# Flipdot_segment.net
KiCad netlist of a schematic drawn in EAGLE
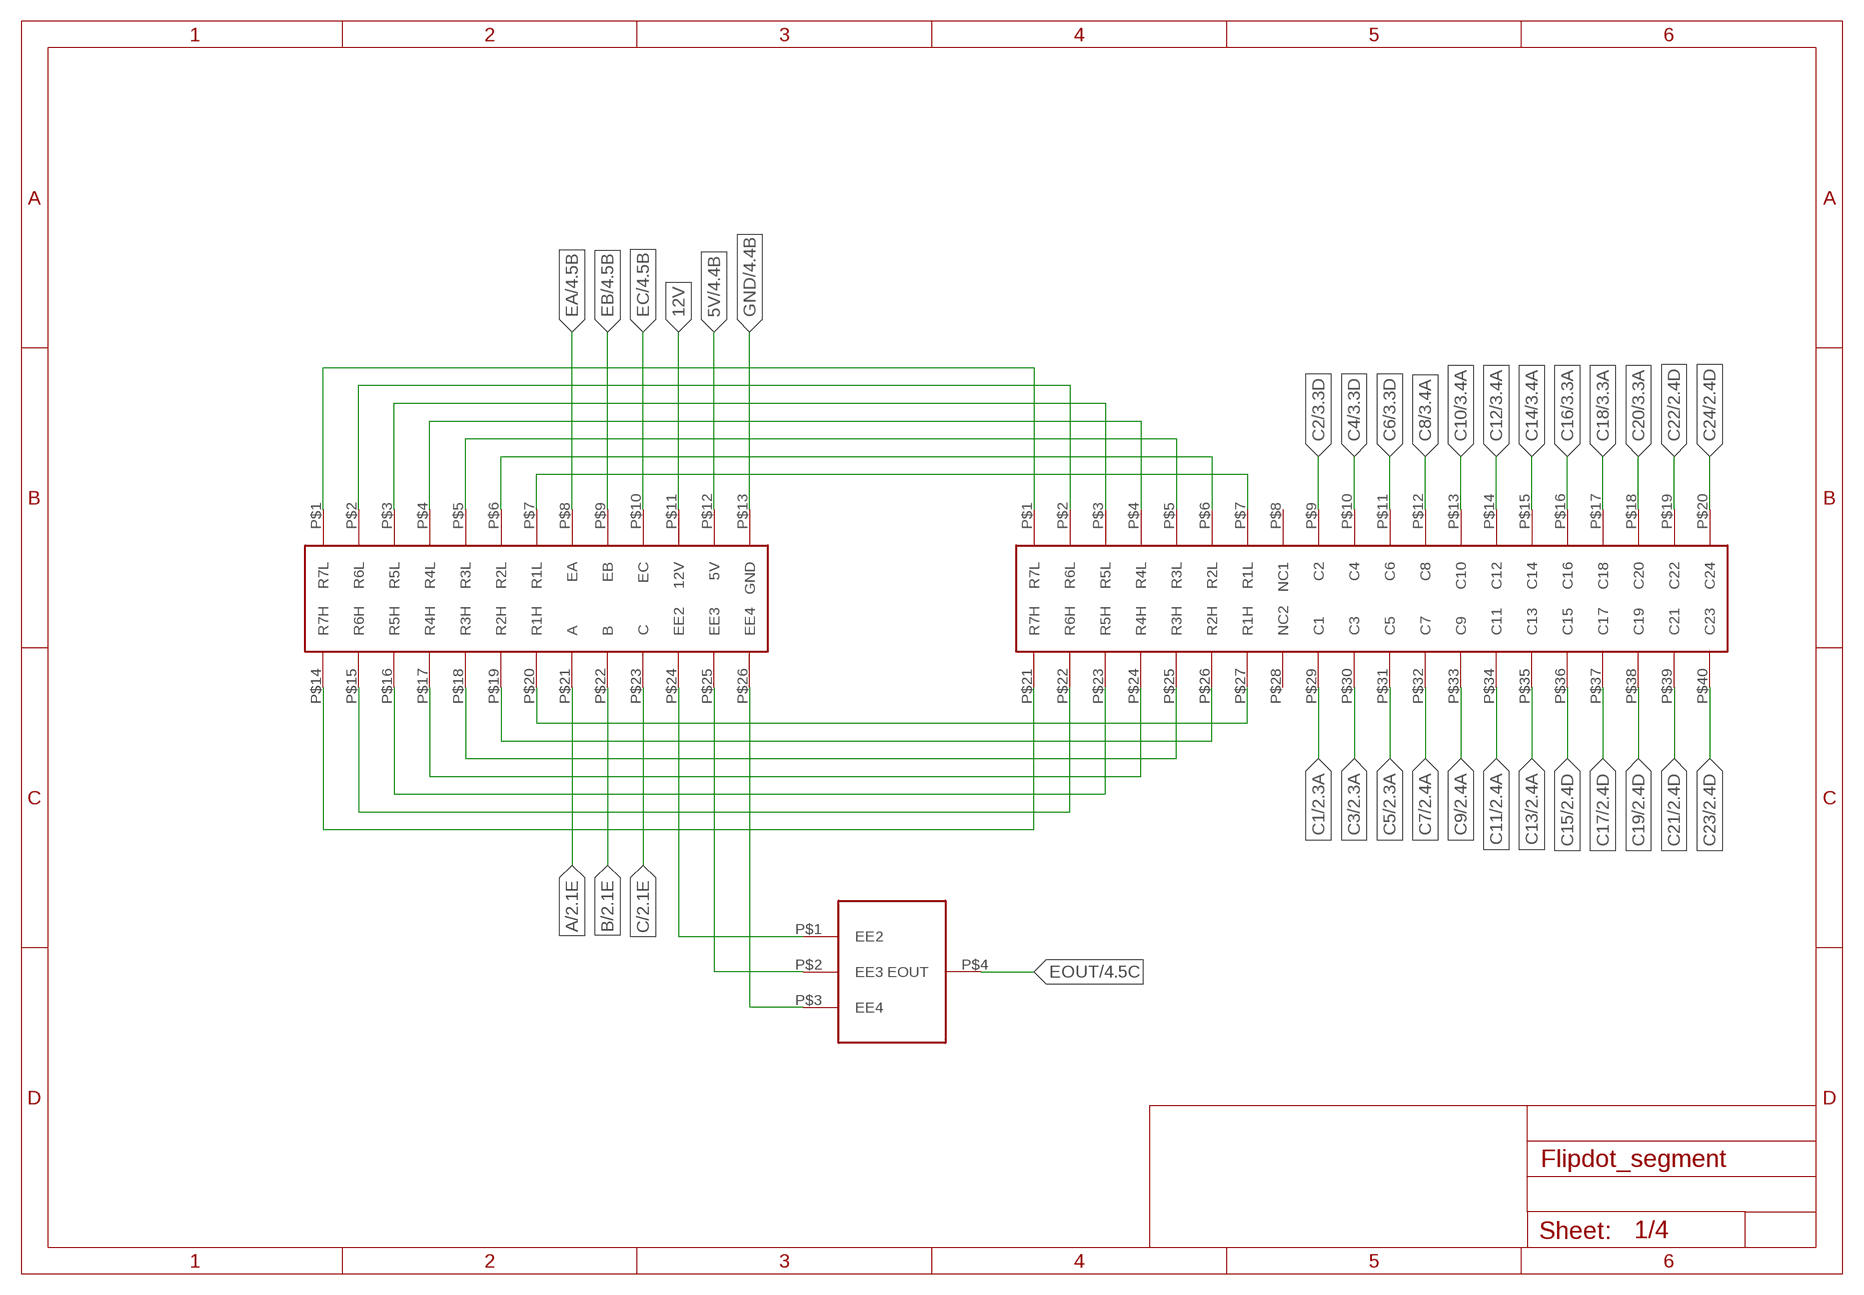
[diagram p0: schematic, sheet 1]
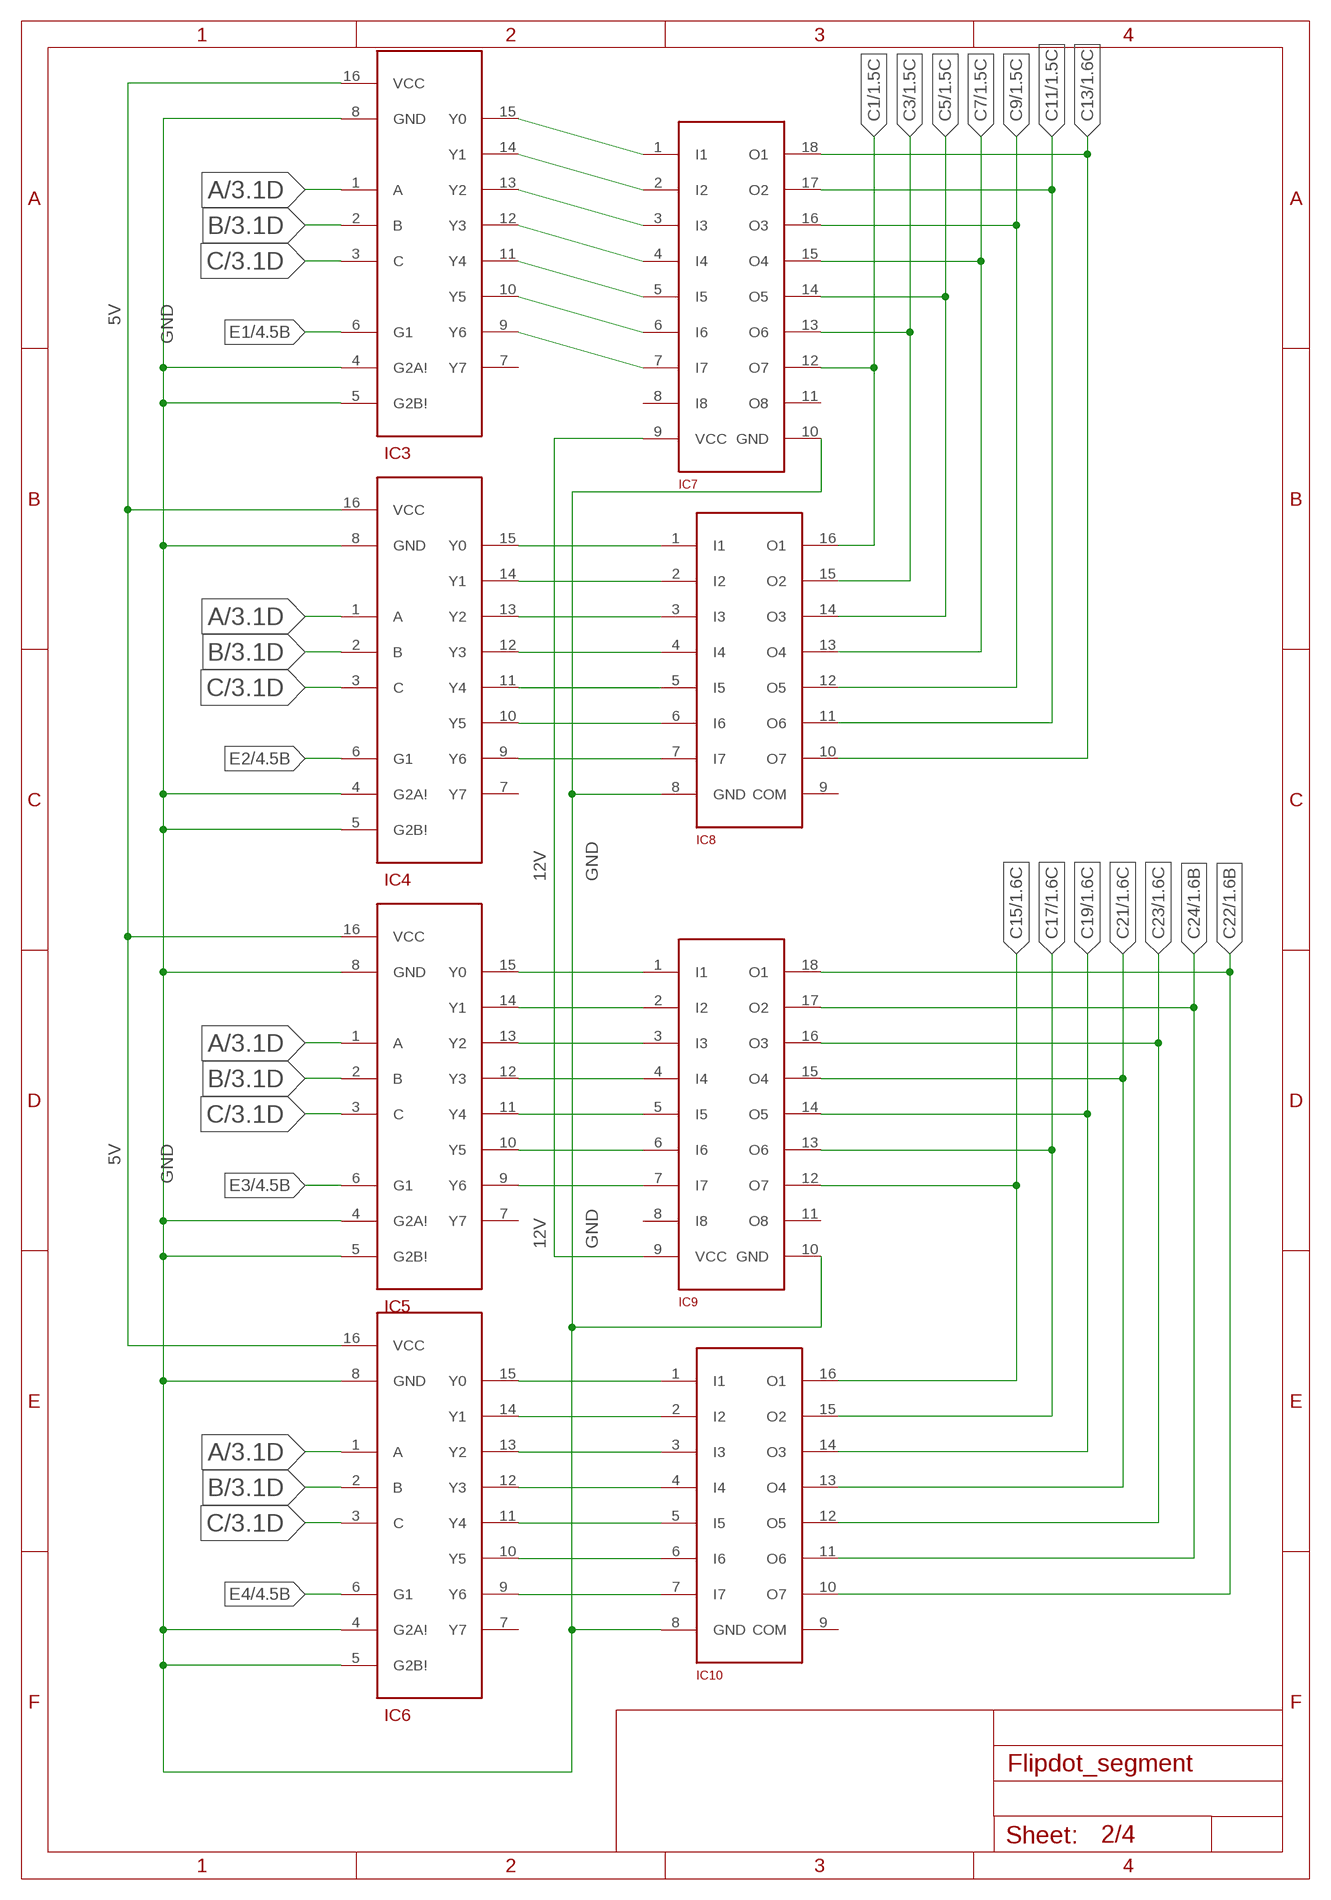
[diagram p1: schematic, sheet 2]
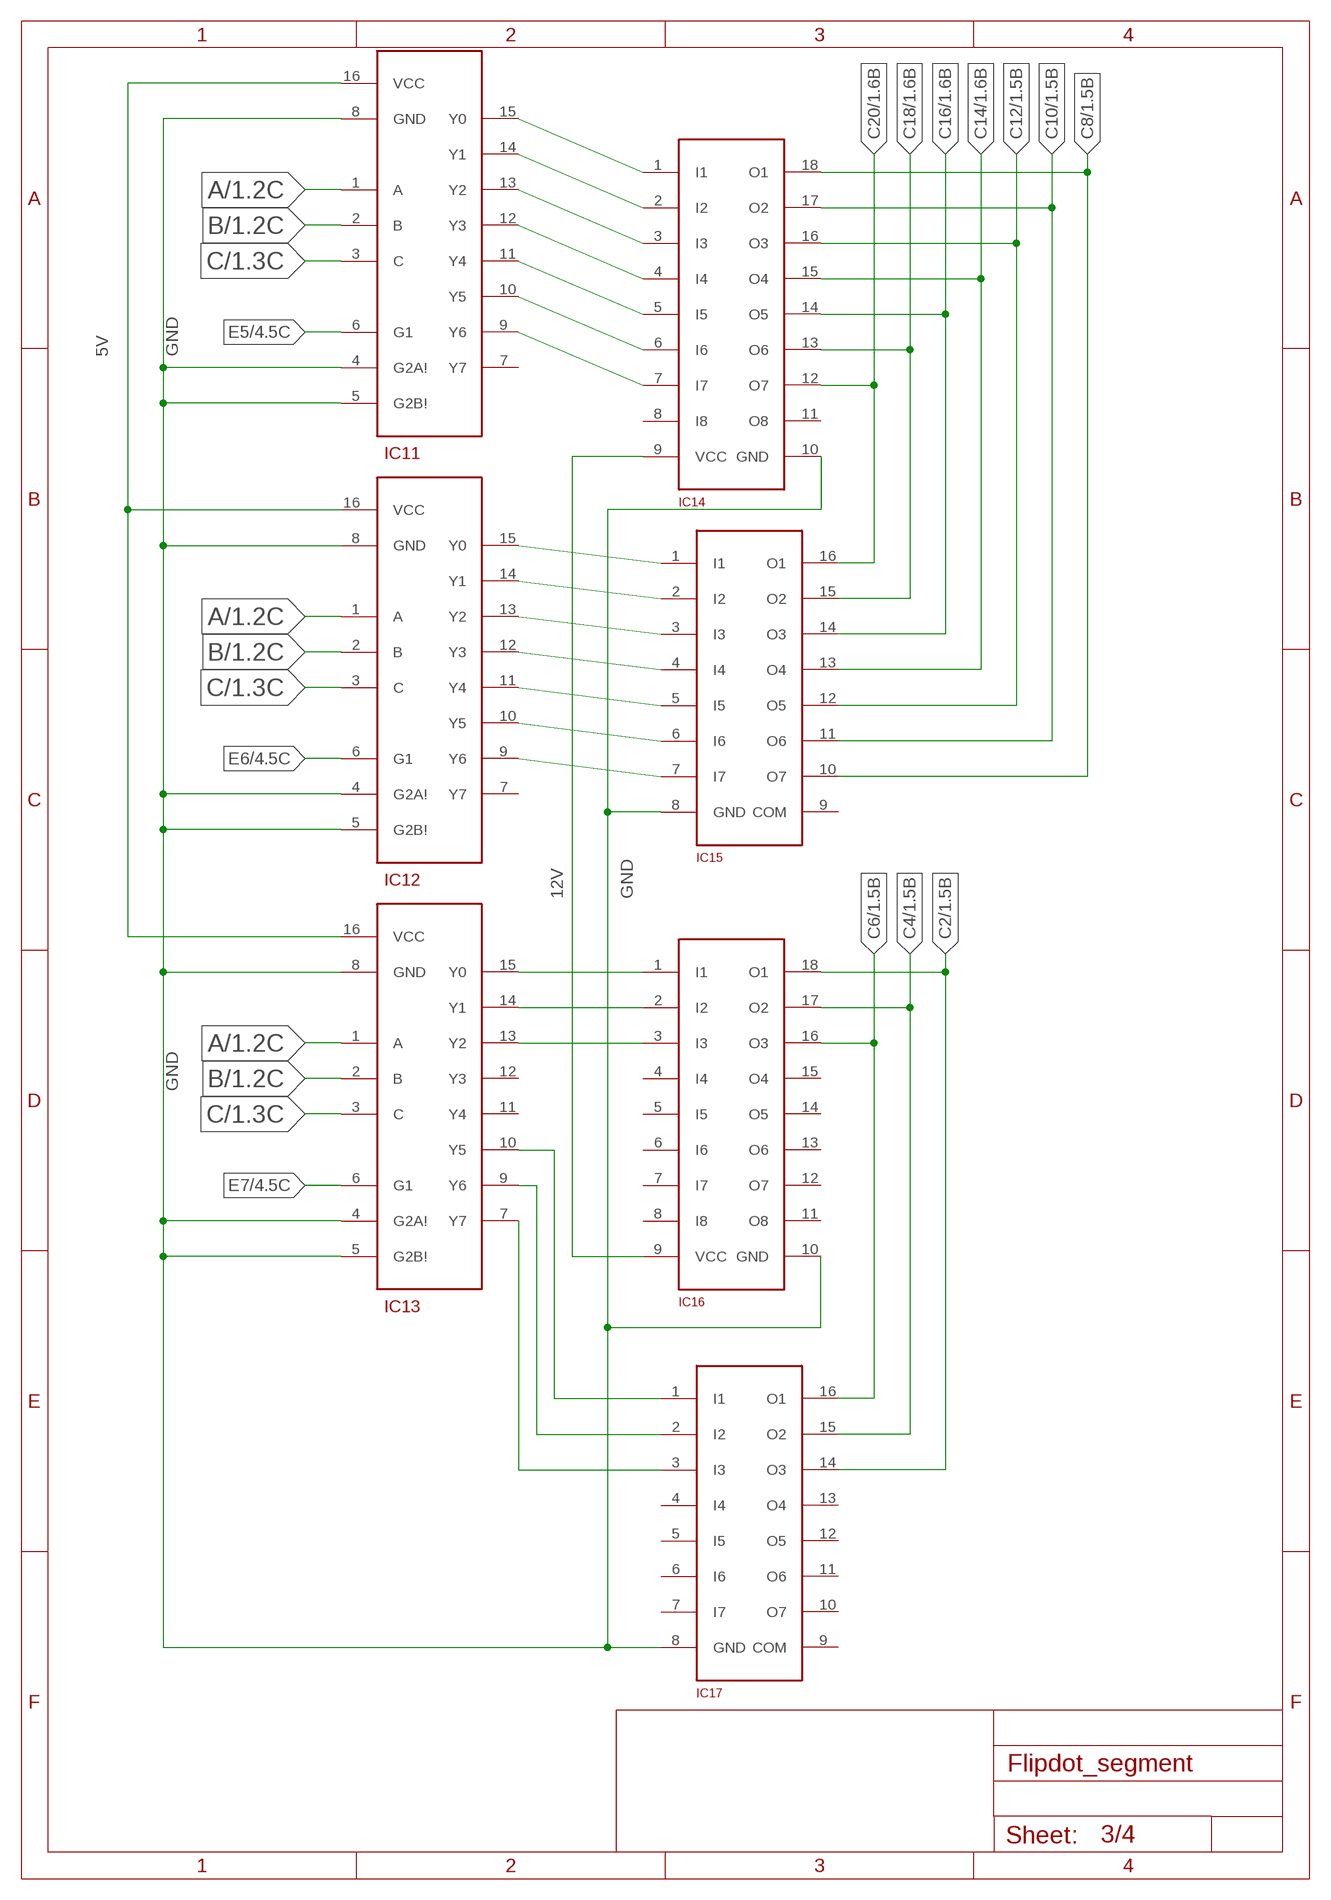
[diagram p2: schematic, sheet 3]
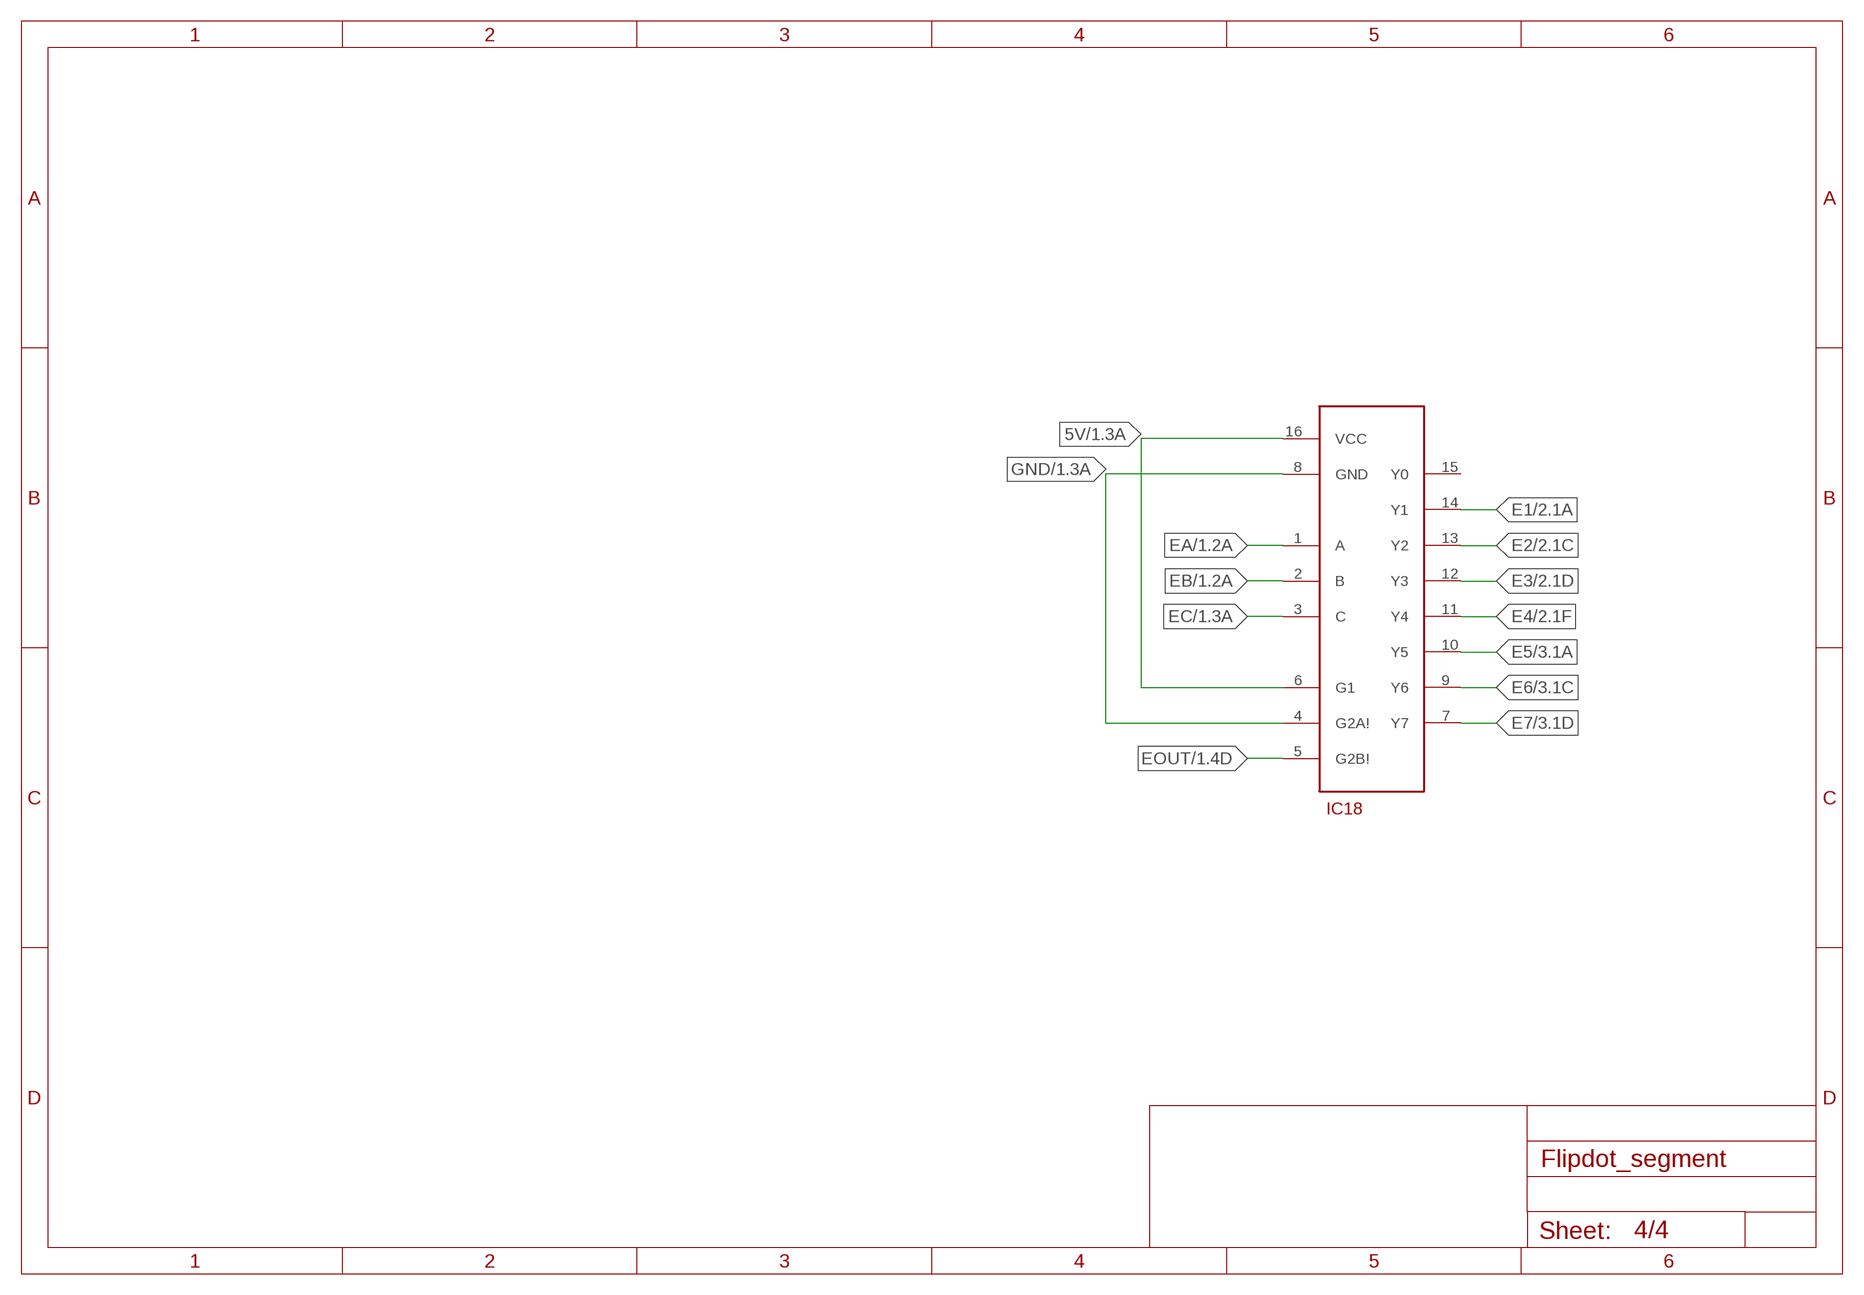
[diagram p3: schematic, sheet 4]

(export (version "E")
  (design (tool "Eeschema 10.0.6"))
  (components
    (comp (ref "IC3")
      (value "M74HC238")
      (footprint "eagle-import:SO16")
      (libsource (lib "eagle-import") (part "M74HC238"))
    )
    (comp (ref "IC4")
      (value "M74HC238")
      (footprint "eagle-import:SO16")
      (libsource (lib "eagle-import") (part "M74HC238"))
    )
    (comp (ref "IC5")
      (value "M74HC238")
      (footprint "eagle-import:SO16")
      (libsource (lib "eagle-import") (part "M74HC238"))
    )
    (comp (ref "IC6")
      (value "M74HC238")
      (footprint "eagle-import:SO16")
      (libsource (lib "eagle-import") (part "M74HC238"))
    )
    (comp (ref "IC7")
      (value "TD62783_AFWG")
      (footprint "eagle-import:SO18W")
      (libsource (lib "eagle-import") (part "TD62783_AFWG"))
    )
    (comp (ref "IC8")
      (value "ULN2003")
      (footprint "eagle-import:SO16")
      (libsource (lib "eagle-import") (part "ULN2003"))
    )
    (comp (ref "IC9")
      (value "TD62783_AFWG")
      (footprint "eagle-import:SO18W")
      (libsource (lib "eagle-import") (part "TD62783_AFWG"))
    )
    (comp (ref "IC10")
      (value "ULN2003")
      (footprint "eagle-import:SO16")
      (libsource (lib "eagle-import") (part "ULN2003"))
    )
    (comp (ref "IC11")
      (value "M74HC238")
      (footprint "eagle-import:SO16")
      (libsource (lib "eagle-import") (part "M74HC238"))
    )
    (comp (ref "IC12")
      (value "M74HC238")
      (footprint "eagle-import:SO16")
      (libsource (lib "eagle-import") (part "M74HC238"))
    )
    (comp (ref "IC13")
      (value "M74HC238")
      (footprint "eagle-import:SO16")
      (libsource (lib "eagle-import") (part "M74HC238"))
    )
    (comp (ref "IC14")
      (value "TD62783_AFWG")
      (footprint "eagle-import:SO18W")
      (libsource (lib "eagle-import") (part "TD62783_AFWG"))
    )
    (comp (ref "IC15")
      (value "ULN2003")
      (footprint "eagle-import:SO16")
      (libsource (lib "eagle-import") (part "ULN2003"))
    )
    (comp (ref "IC16")
      (value "TD62783_AFWG")
      (footprint "eagle-import:SO18W")
      (libsource (lib "eagle-import") (part "TD62783_AFWG"))
    )
    (comp (ref "IC17")
      (value "ULN2003")
      (footprint "eagle-import:SO16")
      (libsource (lib "eagle-import") (part "ULN2003"))
    )
    (comp (ref "IC18")
      (value "M74HC238")
      (footprint "eagle-import:SO16")
      (libsource (lib "eagle-import") (part "M74HC238"))
    )
    (comp (ref "J1")
      (value "HEADER")
      (footprint "eagle-import:HEADER")
      (libsource (lib "eagle-import") (part "HEADER"))
    )
    (comp (ref "J2")
      (value "HEADER_26")
      (footprint "eagle-import:HEADER_26")
      (libsource (lib "eagle-import") (part "HEADER_26"))
    )
    (comp (ref "J3")
      (value "JUMPER")
      (footprint "eagle-import:JUMPER")
      (libsource (lib "eagle-import") (part "JUMPER"))
    )
  )
  (nets
    (net (code "1") (name "5V") (class "Default")
      (node (ref "IC11") (pin "16") (pinfunction "VCC_16") (pintype "bidirectional"))
      (node (ref "IC12") (pin "16") (pinfunction "VCC_16") (pintype "bidirectional"))
      (node (ref "IC13") (pin "16") (pinfunction "VCC_16") (pintype "bidirectional"))
      (node (ref "IC18") (pin "16") (pinfunction "VCC_16") (pintype "bidirectional"))
      (node (ref "IC18") (pin "6") (pinfunction "G1_6") (pintype "bidirectional"))
      (node (ref "IC3") (pin "16") (pinfunction "VCC_16") (pintype "bidirectional"))
      (node (ref "IC4") (pin "16") (pinfunction "VCC_16") (pintype "bidirectional"))
      (node (ref "IC5") (pin "16") (pinfunction "VCC_16") (pintype "bidirectional"))
      (node (ref "IC6") (pin "16") (pinfunction "VCC_16") (pintype "bidirectional"))
      (node (ref "J2") (pin "P$12") (pinfunction "5V_P$12") (pintype "bidirectional"))
    )
    (net (code "2") (name "12V") (class "Default")
      (node (ref "IC14") (pin "9") (pinfunction "VCC_9") (pintype "bidirectional"))
      (node (ref "IC16") (pin "9") (pinfunction "VCC_9") (pintype "bidirectional"))
      (node (ref "IC7") (pin "9") (pinfunction "VCC_9") (pintype "bidirectional"))
      (node (ref "IC9") (pin "9") (pinfunction "VCC_9") (pintype "bidirectional"))
      (node (ref "J2") (pin "P$11") (pinfunction "12V_P$11") (pintype "bidirectional"))
    )
    (net (code "3") (name "A") (class "Default")
      (node (ref "IC11") (pin "1") (pinfunction "A_1") (pintype "bidirectional"))
      (node (ref "IC12") (pin "1") (pinfunction "A_1") (pintype "bidirectional"))
      (node (ref "IC13") (pin "1") (pinfunction "A_1") (pintype "bidirectional"))
      (node (ref "IC3") (pin "1") (pinfunction "A_1") (pintype "bidirectional"))
      (node (ref "IC4") (pin "1") (pinfunction "A_1") (pintype "bidirectional"))
      (node (ref "IC5") (pin "1") (pinfunction "A_1") (pintype "bidirectional"))
      (node (ref "IC6") (pin "1") (pinfunction "A_1") (pintype "bidirectional"))
      (node (ref "J2") (pin "P$21") (pinfunction "A_P$21") (pintype "bidirectional"))
    )
    (net (code "4") (name "B") (class "Default")
      (node (ref "IC11") (pin "2") (pinfunction "B_2") (pintype "bidirectional"))
      (node (ref "IC12") (pin "2") (pinfunction "B_2") (pintype "bidirectional"))
      (node (ref "IC13") (pin "2") (pinfunction "B_2") (pintype "bidirectional"))
      (node (ref "IC3") (pin "2") (pinfunction "B_2") (pintype "bidirectional"))
      (node (ref "IC4") (pin "2") (pinfunction "B_2") (pintype "bidirectional"))
      (node (ref "IC5") (pin "2") (pinfunction "B_2") (pintype "bidirectional"))
      (node (ref "IC6") (pin "2") (pinfunction "B_2") (pintype "bidirectional"))
      (node (ref "J2") (pin "P$22") (pinfunction "B_P$22") (pintype "bidirectional"))
    )
    (net (code "5") (name "C") (class "Default")
      (node (ref "IC11") (pin "3") (pinfunction "C_3") (pintype "bidirectional"))
      (node (ref "IC12") (pin "3") (pinfunction "C_3") (pintype "bidirectional"))
      (node (ref "IC13") (pin "3") (pinfunction "C_3") (pintype "bidirectional"))
      (node (ref "IC3") (pin "3") (pinfunction "C_3") (pintype "bidirectional"))
      (node (ref "IC4") (pin "3") (pinfunction "C_3") (pintype "bidirectional"))
      (node (ref "IC5") (pin "3") (pinfunction "C_3") (pintype "bidirectional"))
      (node (ref "IC6") (pin "3") (pinfunction "C_3") (pintype "bidirectional"))
      (node (ref "J2") (pin "P$23") (pinfunction "C_P$23") (pintype "bidirectional"))
    )
    (net (code "6") (name "C1") (class "Default")
      (node (ref "IC7") (pin "12") (pinfunction "O7_12") (pintype "bidirectional"))
      (node (ref "IC8") (pin "16") (pinfunction "O1_16") (pintype "bidirectional"))
      (node (ref "J1") (pin "P$29") (pinfunction "C1_P$29") (pintype "bidirectional"))
    )
    (net (code "7") (name "C2") (class "Default")
      (node (ref "IC16") (pin "18") (pinfunction "O1_18") (pintype "bidirectional"))
      (node (ref "IC17") (pin "14") (pinfunction "O3_14") (pintype "bidirectional"))
      (node (ref "J1") (pin "P$9") (pinfunction "C2_P$9") (pintype "bidirectional"))
    )
    (net (code "8") (name "C3") (class "Default")
      (node (ref "IC7") (pin "13") (pinfunction "O6_13") (pintype "bidirectional"))
      (node (ref "IC8") (pin "15") (pinfunction "O2_15") (pintype "bidirectional"))
      (node (ref "J1") (pin "P$30") (pinfunction "C3_P$30") (pintype "bidirectional"))
    )
    (net (code "9") (name "C4") (class "Default")
      (node (ref "IC16") (pin "17") (pinfunction "O2_17") (pintype "bidirectional"))
      (node (ref "IC17") (pin "15") (pinfunction "O2_15") (pintype "bidirectional"))
      (node (ref "J1") (pin "P$10") (pinfunction "C4_P$10") (pintype "bidirectional"))
    )
    (net (code "10") (name "C5") (class "Default")
      (node (ref "IC7") (pin "14") (pinfunction "O5_14") (pintype "bidirectional"))
      (node (ref "IC8") (pin "14") (pinfunction "O3_14") (pintype "bidirectional"))
      (node (ref "J1") (pin "P$31") (pinfunction "C5_P$31") (pintype "bidirectional"))
    )
    (net (code "11") (name "C6") (class "Default")
      (node (ref "IC16") (pin "16") (pinfunction "O3_16") (pintype "bidirectional"))
      (node (ref "IC17") (pin "16") (pinfunction "O1_16") (pintype "bidirectional"))
      (node (ref "J1") (pin "P$11") (pinfunction "C6_P$11") (pintype "bidirectional"))
    )
    (net (code "12") (name "C7") (class "Default")
      (node (ref "IC7") (pin "15") (pinfunction "O4_15") (pintype "bidirectional"))
      (node (ref "IC8") (pin "13") (pinfunction "O4_13") (pintype "bidirectional"))
      (node (ref "J1") (pin "P$32") (pinfunction "C7_P$32") (pintype "bidirectional"))
    )
    (net (code "13") (name "C8") (class "Default")
      (node (ref "IC14") (pin "18") (pinfunction "O1_18") (pintype "bidirectional"))
      (node (ref "IC15") (pin "10") (pinfunction "O7_10") (pintype "bidirectional"))
      (node (ref "J1") (pin "P$12") (pinfunction "C8_P$12") (pintype "bidirectional"))
    )
    (net (code "14") (name "C9") (class "Default")
      (node (ref "IC7") (pin "16") (pinfunction "O3_16") (pintype "bidirectional"))
      (node (ref "IC8") (pin "12") (pinfunction "O5_12") (pintype "bidirectional"))
      (node (ref "J1") (pin "P$33") (pinfunction "C9_P$33") (pintype "bidirectional"))
    )
    (net (code "15") (name "C10") (class "Default")
      (node (ref "IC14") (pin "17") (pinfunction "O2_17") (pintype "bidirectional"))
      (node (ref "IC15") (pin "11") (pinfunction "O6_11") (pintype "bidirectional"))
      (node (ref "J1") (pin "P$13") (pinfunction "C10_P$13") (pintype "bidirectional"))
    )
    (net (code "16") (name "C11") (class "Default")
      (node (ref "IC7") (pin "17") (pinfunction "O2_17") (pintype "bidirectional"))
      (node (ref "IC8") (pin "11") (pinfunction "O6_11") (pintype "bidirectional"))
      (node (ref "J1") (pin "P$34") (pinfunction "C11_P$34") (pintype "bidirectional"))
    )
    (net (code "17") (name "C12") (class "Default")
      (node (ref "IC14") (pin "16") (pinfunction "O3_16") (pintype "bidirectional"))
      (node (ref "IC15") (pin "12") (pinfunction "O5_12") (pintype "bidirectional"))
      (node (ref "J1") (pin "P$14") (pinfunction "C12_P$14") (pintype "bidirectional"))
    )
    (net (code "18") (name "C13") (class "Default")
      (node (ref "IC7") (pin "18") (pinfunction "O1_18") (pintype "bidirectional"))
      (node (ref "IC8") (pin "10") (pinfunction "O7_10") (pintype "bidirectional"))
      (node (ref "J1") (pin "P$35") (pinfunction "C13_P$35") (pintype "bidirectional"))
    )
    (net (code "19") (name "C14") (class "Default")
      (node (ref "IC14") (pin "15") (pinfunction "O4_15") (pintype "bidirectional"))
      (node (ref "IC15") (pin "13") (pinfunction "O4_13") (pintype "bidirectional"))
      (node (ref "J1") (pin "P$15") (pinfunction "C14_P$15") (pintype "bidirectional"))
    )
    (net (code "20") (name "C15") (class "Default")
      (node (ref "IC10") (pin "16") (pinfunction "O1_16") (pintype "bidirectional"))
      (node (ref "IC9") (pin "12") (pinfunction "O7_12") (pintype "bidirectional"))
      (node (ref "J1") (pin "P$36") (pinfunction "C15_P$36") (pintype "bidirectional"))
    )
    (net (code "21") (name "C16") (class "Default")
      (node (ref "IC14") (pin "14") (pinfunction "O5_14") (pintype "bidirectional"))
      (node (ref "IC15") (pin "14") (pinfunction "O3_14") (pintype "bidirectional"))
      (node (ref "J1") (pin "P$16") (pinfunction "C16_P$16") (pintype "bidirectional"))
    )
    (net (code "22") (name "C17") (class "Default")
      (node (ref "IC10") (pin "15") (pinfunction "O2_15") (pintype "bidirectional"))
      (node (ref "IC9") (pin "13") (pinfunction "O6_13") (pintype "bidirectional"))
      (node (ref "J1") (pin "P$37") (pinfunction "C17_P$37") (pintype "bidirectional"))
    )
    (net (code "23") (name "C18") (class "Default")
      (node (ref "IC14") (pin "13") (pinfunction "O6_13") (pintype "bidirectional"))
      (node (ref "IC15") (pin "15") (pinfunction "O2_15") (pintype "bidirectional"))
      (node (ref "J1") (pin "P$17") (pinfunction "C18_P$17") (pintype "bidirectional"))
    )
    (net (code "24") (name "C19") (class "Default")
      (node (ref "IC10") (pin "14") (pinfunction "O3_14") (pintype "bidirectional"))
      (node (ref "IC9") (pin "14") (pinfunction "O5_14") (pintype "bidirectional"))
      (node (ref "J1") (pin "P$38") (pinfunction "C19_P$38") (pintype "bidirectional"))
    )
    (net (code "25") (name "C20") (class "Default")
      (node (ref "IC14") (pin "12") (pinfunction "O7_12") (pintype "bidirectional"))
      (node (ref "IC15") (pin "16") (pinfunction "O1_16") (pintype "bidirectional"))
      (node (ref "J1") (pin "P$18") (pinfunction "C20_P$18") (pintype "bidirectional"))
    )
    (net (code "26") (name "C21") (class "Default")
      (node (ref "IC10") (pin "13") (pinfunction "O4_13") (pintype "bidirectional"))
      (node (ref "IC9") (pin "15") (pinfunction "O4_15") (pintype "bidirectional"))
      (node (ref "J1") (pin "P$39") (pinfunction "C21_P$39") (pintype "bidirectional"))
    )
    (net (code "27") (name "C22") (class "Default")
      (node (ref "IC10") (pin "10") (pinfunction "O7_10") (pintype "bidirectional"))
      (node (ref "IC9") (pin "18") (pinfunction "O1_18") (pintype "bidirectional"))
      (node (ref "J1") (pin "P$19") (pinfunction "C22_P$19") (pintype "bidirectional"))
    )
    (net (code "28") (name "C23") (class "Default")
      (node (ref "IC10") (pin "12") (pinfunction "O5_12") (pintype "bidirectional"))
      (node (ref "IC9") (pin "16") (pinfunction "O3_16") (pintype "bidirectional"))
      (node (ref "J1") (pin "P$40") (pinfunction "C23_P$40") (pintype "bidirectional"))
    )
    (net (code "29") (name "C24") (class "Default")
      (node (ref "IC10") (pin "11") (pinfunction "O6_11") (pintype "bidirectional"))
      (node (ref "IC9") (pin "17") (pinfunction "O2_17") (pintype "bidirectional"))
      (node (ref "J1") (pin "P$20") (pinfunction "C24_P$20") (pintype "bidirectional"))
    )
    (net (code "30") (name "E1") (class "Default")
      (node (ref "IC18") (pin "14") (pinfunction "Y1_14") (pintype "bidirectional"))
      (node (ref "IC3") (pin "6") (pinfunction "G1_6") (pintype "bidirectional"))
    )
    (net (code "31") (name "E2") (class "Default")
      (node (ref "IC18") (pin "13") (pinfunction "Y2_13") (pintype "bidirectional"))
      (node (ref "IC4") (pin "6") (pinfunction "G1_6") (pintype "bidirectional"))
    )
    (net (code "32") (name "E3") (class "Default")
      (node (ref "IC18") (pin "12") (pinfunction "Y3_12") (pintype "bidirectional"))
      (node (ref "IC5") (pin "6") (pinfunction "G1_6") (pintype "bidirectional"))
    )
    (net (code "33") (name "E4") (class "Default")
      (node (ref "IC18") (pin "11") (pinfunction "Y4_11") (pintype "bidirectional"))
      (node (ref "IC6") (pin "6") (pinfunction "G1_6") (pintype "bidirectional"))
    )
    (net (code "34") (name "E5") (class "Default")
      (node (ref "IC11") (pin "6") (pinfunction "G1_6") (pintype "bidirectional"))
      (node (ref "IC18") (pin "10") (pinfunction "Y5_10") (pintype "bidirectional"))
    )
    (net (code "35") (name "E6") (class "Default")
      (node (ref "IC12") (pin "6") (pinfunction "G1_6") (pintype "bidirectional"))
      (node (ref "IC18") (pin "9") (pinfunction "Y6_9") (pintype "bidirectional"))
    )
    (net (code "36") (name "E7") (class "Default")
      (node (ref "IC13") (pin "6") (pinfunction "G1_6") (pintype "bidirectional"))
      (node (ref "IC18") (pin "7") (pinfunction "Y7_7") (pintype "bidirectional"))
    )
    (net (code "37") (name "EA") (class "Default")
      (node (ref "IC18") (pin "1") (pinfunction "A_1") (pintype "bidirectional"))
      (node (ref "J2") (pin "P$8") (pinfunction "EA_P$8") (pintype "bidirectional"))
    )
    (net (code "38") (name "EB") (class "Default")
      (node (ref "IC18") (pin "2") (pinfunction "B_2") (pintype "bidirectional"))
      (node (ref "J2") (pin "P$9") (pinfunction "EB_P$9") (pintype "bidirectional"))
    )
    (net (code "39") (name "EC") (class "Default")
      (node (ref "IC18") (pin "3") (pinfunction "C_3") (pintype "bidirectional"))
      (node (ref "J2") (pin "P$10") (pinfunction "EC_P$10") (pintype "bidirectional"))
    )
    (net (code "40") (name "EOUT") (class "Default")
      (node (ref "IC18") (pin "5") (pinfunction "G2B~{}_5") (pintype "bidirectional"))
      (node (ref "J3") (pin "P$4") (pinfunction "EOUT_P$4") (pintype "bidirectional"))
    )
    (net (code "41") (name "GND") (class "Default")
      (node (ref "IC10") (pin "8") (pinfunction "GND_8") (pintype "bidirectional"))
      (node (ref "IC11") (pin "4") (pinfunction "G2A~{}_4") (pintype "bidirectional"))
      (node (ref "IC11") (pin "5") (pinfunction "G2B~{}_5") (pintype "bidirectional"))
      (node (ref "IC11") (pin "8") (pinfunction "GND_8") (pintype "bidirectional"))
      (node (ref "IC12") (pin "4") (pinfunction "G2A~{}_4") (pintype "bidirectional"))
      (node (ref "IC12") (pin "5") (pinfunction "G2B~{}_5") (pintype "bidirectional"))
      (node (ref "IC12") (pin "8") (pinfunction "GND_8") (pintype "bidirectional"))
      (node (ref "IC13") (pin "4") (pinfunction "G2A~{}_4") (pintype "bidirectional"))
      (node (ref "IC13") (pin "5") (pinfunction "G2B~{}_5") (pintype "bidirectional"))
      (node (ref "IC13") (pin "8") (pinfunction "GND_8") (pintype "bidirectional"))
      (node (ref "IC14") (pin "10") (pinfunction "GND_10") (pintype "bidirectional"))
      (node (ref "IC15") (pin "8") (pinfunction "GND_8") (pintype "bidirectional"))
      (node (ref "IC16") (pin "10") (pinfunction "GND_10") (pintype "bidirectional"))
      (node (ref "IC17") (pin "8") (pinfunction "GND_8") (pintype "bidirectional"))
      (node (ref "IC18") (pin "4") (pinfunction "G2A~{}_4") (pintype "bidirectional"))
      (node (ref "IC18") (pin "8") (pinfunction "GND_8") (pintype "bidirectional"))
      (node (ref "IC3") (pin "4") (pinfunction "G2A~{}_4") (pintype "bidirectional"))
      (node (ref "IC3") (pin "5") (pinfunction "G2B~{}_5") (pintype "bidirectional"))
      (node (ref "IC3") (pin "8") (pinfunction "GND_8") (pintype "bidirectional"))
      (node (ref "IC4") (pin "4") (pinfunction "G2A~{}_4") (pintype "bidirectional"))
      (node (ref "IC4") (pin "5") (pinfunction "G2B~{}_5") (pintype "bidirectional"))
      (node (ref "IC4") (pin "8") (pinfunction "GND_8") (pintype "bidirectional"))
      (node (ref "IC5") (pin "4") (pinfunction "G2A~{}_4") (pintype "bidirectional"))
      (node (ref "IC5") (pin "5") (pinfunction "G2B~{}_5") (pintype "bidirectional"))
      (node (ref "IC5") (pin "8") (pinfunction "GND_8") (pintype "bidirectional"))
      (node (ref "IC6") (pin "4") (pinfunction "G2A~{}_4") (pintype "bidirectional"))
      (node (ref "IC6") (pin "5") (pinfunction "G2B~{}_5") (pintype "bidirectional"))
      (node (ref "IC6") (pin "8") (pinfunction "GND_8") (pintype "bidirectional"))
      (node (ref "IC7") (pin "10") (pinfunction "GND_10") (pintype "bidirectional"))
      (node (ref "IC8") (pin "8") (pinfunction "GND_8") (pintype "bidirectional"))
      (node (ref "IC9") (pin "10") (pinfunction "GND_10") (pintype "bidirectional"))
      (node (ref "J2") (pin "P$13") (pinfunction "GND_P$13") (pintype "bidirectional"))
    )
    (net (code "42") (name "Net-(IC3-Y0)") (class "Default")
      (node (ref "IC3") (pin "15") (pinfunction "Y0_15") (pintype "bidirectional"))
      (node (ref "IC7") (pin "1") (pinfunction "I1_1") (pintype "bidirectional"))
    )
    (net (code "43") (name "Net-(IC3-Y1)") (class "Default")
      (node (ref "IC3") (pin "14") (pinfunction "Y1_14") (pintype "bidirectional"))
      (node (ref "IC7") (pin "2") (pinfunction "I2_2") (pintype "bidirectional"))
    )
    (net (code "44") (name "Net-(IC3-Y2)") (class "Default")
      (node (ref "IC3") (pin "13") (pinfunction "Y2_13") (pintype "bidirectional"))
      (node (ref "IC7") (pin "3") (pinfunction "I3_3") (pintype "bidirectional"))
    )
    (net (code "45") (name "Net-(IC3-Y3)") (class "Default")
      (node (ref "IC3") (pin "12") (pinfunction "Y3_12") (pintype "bidirectional"))
      (node (ref "IC7") (pin "4") (pinfunction "I4_4") (pintype "bidirectional"))
    )
    (net (code "46") (name "Net-(IC3-Y4)") (class "Default")
      (node (ref "IC3") (pin "11") (pinfunction "Y4_11") (pintype "bidirectional"))
      (node (ref "IC7") (pin "5") (pinfunction "I5_5") (pintype "bidirectional"))
    )
    (net (code "47") (name "Net-(IC3-Y5)") (class "Default")
      (node (ref "IC3") (pin "10") (pinfunction "Y5_10") (pintype "bidirectional"))
      (node (ref "IC7") (pin "6") (pinfunction "I6_6") (pintype "bidirectional"))
    )
    (net (code "48") (name "Net-(IC3-Y6)") (class "Default")
      (node (ref "IC3") (pin "9") (pinfunction "Y6_9") (pintype "bidirectional"))
      (node (ref "IC7") (pin "7") (pinfunction "I7_7") (pintype "bidirectional"))
    )
    (net (code "49") (name "Net-(IC4-Y0)") (class "Default")
      (node (ref "IC4") (pin "15") (pinfunction "Y0_15") (pintype "bidirectional"))
      (node (ref "IC8") (pin "1") (pinfunction "I1_1") (pintype "bidirectional"))
    )
    (net (code "50") (name "Net-(IC4-Y1)") (class "Default")
      (node (ref "IC4") (pin "14") (pinfunction "Y1_14") (pintype "bidirectional"))
      (node (ref "IC8") (pin "2") (pinfunction "I2_2") (pintype "bidirectional"))
    )
    (net (code "51") (name "Net-(IC4-Y2)") (class "Default")
      (node (ref "IC4") (pin "13") (pinfunction "Y2_13") (pintype "bidirectional"))
      (node (ref "IC8") (pin "3") (pinfunction "I3_3") (pintype "bidirectional"))
    )
    (net (code "52") (name "Net-(IC4-Y3)") (class "Default")
      (node (ref "IC4") (pin "12") (pinfunction "Y3_12") (pintype "bidirectional"))
      (node (ref "IC8") (pin "4") (pinfunction "I4_4") (pintype "bidirectional"))
    )
    (net (code "53") (name "Net-(IC4-Y4)") (class "Default")
      (node (ref "IC4") (pin "11") (pinfunction "Y4_11") (pintype "bidirectional"))
      (node (ref "IC8") (pin "5") (pinfunction "I5_5") (pintype "bidirectional"))
    )
    (net (code "54") (name "Net-(IC4-Y5)") (class "Default")
      (node (ref "IC4") (pin "10") (pinfunction "Y5_10") (pintype "bidirectional"))
      (node (ref "IC8") (pin "6") (pinfunction "I6_6") (pintype "bidirectional"))
    )
    (net (code "55") (name "Net-(IC4-Y6)") (class "Default")
      (node (ref "IC4") (pin "9") (pinfunction "Y6_9") (pintype "bidirectional"))
      (node (ref "IC8") (pin "7") (pinfunction "I7_7") (pintype "bidirectional"))
    )
    (net (code "56") (name "Net-(IC5-Y0)") (class "Default")
      (node (ref "IC5") (pin "15") (pinfunction "Y0_15") (pintype "bidirectional"))
      (node (ref "IC9") (pin "1") (pinfunction "I1_1") (pintype "bidirectional"))
    )
    (net (code "57") (name "Net-(IC5-Y1)") (class "Default")
      (node (ref "IC5") (pin "14") (pinfunction "Y1_14") (pintype "bidirectional"))
      (node (ref "IC9") (pin "2") (pinfunction "I2_2") (pintype "bidirectional"))
    )
    (net (code "58") (name "Net-(IC5-Y2)") (class "Default")
      (node (ref "IC5") (pin "13") (pinfunction "Y2_13") (pintype "bidirectional"))
      (node (ref "IC9") (pin "3") (pinfunction "I3_3") (pintype "bidirectional"))
    )
    (net (code "59") (name "Net-(IC5-Y3)") (class "Default")
      (node (ref "IC5") (pin "12") (pinfunction "Y3_12") (pintype "bidirectional"))
      (node (ref "IC9") (pin "4") (pinfunction "I4_4") (pintype "bidirectional"))
    )
    (net (code "60") (name "Net-(IC5-Y4)") (class "Default")
      (node (ref "IC5") (pin "11") (pinfunction "Y4_11") (pintype "bidirectional"))
      (node (ref "IC9") (pin "5") (pinfunction "I5_5") (pintype "bidirectional"))
    )
    (net (code "61") (name "Net-(IC5-Y5)") (class "Default")
      (node (ref "IC5") (pin "10") (pinfunction "Y5_10") (pintype "bidirectional"))
      (node (ref "IC9") (pin "6") (pinfunction "I6_6") (pintype "bidirectional"))
    )
    (net (code "62") (name "Net-(IC5-Y6)") (class "Default")
      (node (ref "IC5") (pin "9") (pinfunction "Y6_9") (pintype "bidirectional"))
      (node (ref "IC9") (pin "7") (pinfunction "I7_7") (pintype "bidirectional"))
    )
    (net (code "63") (name "Net-(IC10-I1)") (class "Default")
      (node (ref "IC10") (pin "1") (pinfunction "I1_1") (pintype "bidirectional"))
      (node (ref "IC6") (pin "15") (pinfunction "Y0_15") (pintype "bidirectional"))
    )
    (net (code "64") (name "Net-(IC10-I2)") (class "Default")
      (node (ref "IC10") (pin "2") (pinfunction "I2_2") (pintype "bidirectional"))
      (node (ref "IC6") (pin "14") (pinfunction "Y1_14") (pintype "bidirectional"))
    )
    (net (code "65") (name "Net-(IC10-I3)") (class "Default")
      (node (ref "IC10") (pin "3") (pinfunction "I3_3") (pintype "bidirectional"))
      (node (ref "IC6") (pin "13") (pinfunction "Y2_13") (pintype "bidirectional"))
    )
    (net (code "66") (name "Net-(IC10-I4)") (class "Default")
      (node (ref "IC10") (pin "4") (pinfunction "I4_4") (pintype "bidirectional"))
      (node (ref "IC6") (pin "12") (pinfunction "Y3_12") (pintype "bidirectional"))
    )
    (net (code "67") (name "Net-(IC10-I5)") (class "Default")
      (node (ref "IC10") (pin "5") (pinfunction "I5_5") (pintype "bidirectional"))
      (node (ref "IC6") (pin "11") (pinfunction "Y4_11") (pintype "bidirectional"))
    )
    (net (code "68") (name "Net-(IC10-I6)") (class "Default")
      (node (ref "IC10") (pin "6") (pinfunction "I6_6") (pintype "bidirectional"))
      (node (ref "IC6") (pin "10") (pinfunction "Y5_10") (pintype "bidirectional"))
    )
    (net (code "69") (name "Net-(IC10-I7)") (class "Default")
      (node (ref "IC10") (pin "7") (pinfunction "I7_7") (pintype "bidirectional"))
      (node (ref "IC6") (pin "9") (pinfunction "Y6_9") (pintype "bidirectional"))
    )
    (net (code "70") (name "Net-(IC11-Y0)") (class "Default")
      (node (ref "IC11") (pin "15") (pinfunction "Y0_15") (pintype "bidirectional"))
      (node (ref "IC14") (pin "1") (pinfunction "I1_1") (pintype "bidirectional"))
    )
    (net (code "71") (name "Net-(IC11-Y1)") (class "Default")
      (node (ref "IC11") (pin "14") (pinfunction "Y1_14") (pintype "bidirectional"))
      (node (ref "IC14") (pin "2") (pinfunction "I2_2") (pintype "bidirectional"))
    )
    (net (code "72") (name "Net-(IC11-Y2)") (class "Default")
      (node (ref "IC11") (pin "13") (pinfunction "Y2_13") (pintype "bidirectional"))
      (node (ref "IC14") (pin "3") (pinfunction "I3_3") (pintype "bidirectional"))
    )
    (net (code "73") (name "Net-(IC11-Y3)") (class "Default")
      (node (ref "IC11") (pin "12") (pinfunction "Y3_12") (pintype "bidirectional"))
      (node (ref "IC14") (pin "4") (pinfunction "I4_4") (pintype "bidirectional"))
    )
    (net (code "74") (name "Net-(IC11-Y4)") (class "Default")
      (node (ref "IC11") (pin "11") (pinfunction "Y4_11") (pintype "bidirectional"))
      (node (ref "IC14") (pin "5") (pinfunction "I5_5") (pintype "bidirectional"))
    )
    (net (code "75") (name "Net-(IC11-Y5)") (class "Default")
      (node (ref "IC11") (pin "10") (pinfunction "Y5_10") (pintype "bidirectional"))
      (node (ref "IC14") (pin "6") (pinfunction "I6_6") (pintype "bidirectional"))
    )
    (net (code "76") (name "Net-(IC11-Y6)") (class "Default")
      (node (ref "IC11") (pin "9") (pinfunction "Y6_9") (pintype "bidirectional"))
      (node (ref "IC14") (pin "7") (pinfunction "I7_7") (pintype "bidirectional"))
    )
    (net (code "77") (name "Net-(IC12-Y0)") (class "Default")
      (node (ref "IC12") (pin "15") (pinfunction "Y0_15") (pintype "bidirectional"))
      (node (ref "IC15") (pin "1") (pinfunction "I1_1") (pintype "bidirectional"))
    )
    (net (code "78") (name "Net-(IC12-Y1)") (class "Default")
      (node (ref "IC12") (pin "14") (pinfunction "Y1_14") (pintype "bidirectional"))
      (node (ref "IC15") (pin "2") (pinfunction "I2_2") (pintype "bidirectional"))
    )
    (net (code "79") (name "Net-(IC12-Y2)") (class "Default")
      (node (ref "IC12") (pin "13") (pinfunction "Y2_13") (pintype "bidirectional"))
      (node (ref "IC15") (pin "3") (pinfunction "I3_3") (pintype "bidirectional"))
    )
    (net (code "80") (name "Net-(IC12-Y3)") (class "Default")
      (node (ref "IC12") (pin "12") (pinfunction "Y3_12") (pintype "bidirectional"))
      (node (ref "IC15") (pin "4") (pinfunction "I4_4") (pintype "bidirectional"))
    )
    (net (code "81") (name "Net-(IC12-Y4)") (class "Default")
      (node (ref "IC12") (pin "11") (pinfunction "Y4_11") (pintype "bidirectional"))
      (node (ref "IC15") (pin "5") (pinfunction "I5_5") (pintype "bidirectional"))
    )
    (net (code "82") (name "Net-(IC12-Y5)") (class "Default")
      (node (ref "IC12") (pin "10") (pinfunction "Y5_10") (pintype "bidirectional"))
      (node (ref "IC15") (pin "6") (pinfunction "I6_6") (pintype "bidirectional"))
    )
    (net (code "83") (name "Net-(IC12-Y6)") (class "Default")
      (node (ref "IC12") (pin "9") (pinfunction "Y6_9") (pintype "bidirectional"))
      (node (ref "IC15") (pin "7") (pinfunction "I7_7") (pintype "bidirectional"))
    )
    (net (code "84") (name "Net-(IC13-Y0)") (class "Default")
      (node (ref "IC13") (pin "15") (pinfunction "Y0_15") (pintype "bidirectional"))
      (node (ref "IC16") (pin "1") (pinfunction "I1_1") (pintype "bidirectional"))
    )
    (net (code "85") (name "Net-(IC13-Y1)") (class "Default")
      (node (ref "IC13") (pin "14") (pinfunction "Y1_14") (pintype "bidirectional"))
      (node (ref "IC16") (pin "2") (pinfunction "I2_2") (pintype "bidirectional"))
    )
    (net (code "86") (name "Net-(IC13-Y2)") (class "Default")
      (node (ref "IC13") (pin "13") (pinfunction "Y2_13") (pintype "bidirectional"))
      (node (ref "IC16") (pin "3") (pinfunction "I3_3") (pintype "bidirectional"))
    )
    (net (code "87") (name "Net-(IC13-Y5)") (class "Default")
      (node (ref "IC13") (pin "10") (pinfunction "Y5_10") (pintype "bidirectional"))
      (node (ref "IC17") (pin "1") (pinfunction "I1_1") (pintype "bidirectional"))
    )
    (net (code "88") (name "Net-(IC13-Y6)") (class "Default")
      (node (ref "IC13") (pin "9") (pinfunction "Y6_9") (pintype "bidirectional"))
      (node (ref "IC17") (pin "2") (pinfunction "I2_2") (pintype "bidirectional"))
    )
    (net (code "89") (name "Net-(IC13-Y7)") (class "Default")
      (node (ref "IC13") (pin "7") (pinfunction "Y7_7") (pintype "bidirectional"))
      (node (ref "IC17") (pin "3") (pinfunction "I3_3") (pintype "bidirectional"))
    )
    (net (code "90") (name "Net-(J1-R1H)") (class "Default")
      (node (ref "J1") (pin "P$27") (pinfunction "R1H_P$27") (pintype "bidirectional"))
      (node (ref "J2") (pin "P$20") (pinfunction "R1H_P$20") (pintype "bidirectional"))
    )
    (net (code "91") (name "Net-(J1-R1L)") (class "Default")
      (node (ref "J1") (pin "P$7") (pinfunction "R1L_P$7") (pintype "bidirectional"))
      (node (ref "J2") (pin "P$7") (pinfunction "R1L_P$7") (pintype "bidirectional"))
    )
    (net (code "92") (name "Net-(J1-R2H)") (class "Default")
      (node (ref "J1") (pin "P$26") (pinfunction "R2H_P$26") (pintype "bidirectional"))
      (node (ref "J2") (pin "P$19") (pinfunction "R2H_P$19") (pintype "bidirectional"))
    )
    (net (code "93") (name "Net-(J1-R2L)") (class "Default")
      (node (ref "J1") (pin "P$6") (pinfunction "R2L_P$6") (pintype "bidirectional"))
      (node (ref "J2") (pin "P$6") (pinfunction "R2L_P$6") (pintype "bidirectional"))
    )
    (net (code "94") (name "Net-(J1-R3H)") (class "Default")
      (node (ref "J1") (pin "P$25") (pinfunction "R3H_P$25") (pintype "bidirectional"))
      (node (ref "J2") (pin "P$18") (pinfunction "R3H_P$18") (pintype "bidirectional"))
    )
    (net (code "95") (name "Net-(J1-R3L)") (class "Default")
      (node (ref "J1") (pin "P$5") (pinfunction "R3L_P$5") (pintype "bidirectional"))
      (node (ref "J2") (pin "P$5") (pinfunction "R3L_P$5") (pintype "bidirectional"))
    )
    (net (code "96") (name "Net-(J1-R4H)") (class "Default")
      (node (ref "J1") (pin "P$24") (pinfunction "R4H_P$24") (pintype "bidirectional"))
      (node (ref "J2") (pin "P$17") (pinfunction "R4H_P$17") (pintype "bidirectional"))
    )
    (net (code "97") (name "Net-(J1-R4L)") (class "Default")
      (node (ref "J1") (pin "P$4") (pinfunction "R4L_P$4") (pintype "bidirectional"))
      (node (ref "J2") (pin "P$4") (pinfunction "R4L_P$4") (pintype "bidirectional"))
    )
    (net (code "98") (name "Net-(J1-R5H)") (class "Default")
      (node (ref "J1") (pin "P$23") (pinfunction "R5H_P$23") (pintype "bidirectional"))
      (node (ref "J2") (pin "P$16") (pinfunction "R5H_P$16") (pintype "bidirectional"))
    )
    (net (code "99") (name "Net-(J1-R5L)") (class "Default")
      (node (ref "J1") (pin "P$3") (pinfunction "R5L_P$3") (pintype "bidirectional"))
      (node (ref "J2") (pin "P$3") (pinfunction "R5L_P$3") (pintype "bidirectional"))
    )
    (net (code "100") (name "Net-(J1-R6H)") (class "Default")
      (node (ref "J1") (pin "P$22") (pinfunction "R6H_P$22") (pintype "bidirectional"))
      (node (ref "J2") (pin "P$15") (pinfunction "R6H_P$15") (pintype "bidirectional"))
    )
    (net (code "101") (name "Net-(J1-R6L)") (class "Default")
      (node (ref "J1") (pin "P$2") (pinfunction "R6L_P$2") (pintype "bidirectional"))
      (node (ref "J2") (pin "P$2") (pinfunction "R6L_P$2") (pintype "bidirectional"))
    )
    (net (code "102") (name "Net-(J1-R7H)") (class "Default")
      (node (ref "J1") (pin "P$21") (pinfunction "R7H_P$21") (pintype "bidirectional"))
      (node (ref "J2") (pin "P$14") (pinfunction "R7H_P$14") (pintype "bidirectional"))
    )
    (net (code "103") (name "Net-(J1-R7L)") (class "Default")
      (node (ref "J1") (pin "P$1") (pinfunction "R7L_P$1") (pintype "bidirectional"))
      (node (ref "J2") (pin "P$1") (pinfunction "R7L_P$1") (pintype "bidirectional"))
    )
    (net (code "104") (name "Net-(J2-EE2)") (class "Default")
      (node (ref "J2") (pin "P$24") (pinfunction "EE2_P$24") (pintype "bidirectional"))
      (node (ref "J3") (pin "P$1") (pinfunction "EE2_P$1") (pintype "bidirectional"))
    )
    (net (code "105") (name "Net-(J2-EE3)") (class "Default")
      (node (ref "J2") (pin "P$25") (pinfunction "EE3_P$25") (pintype "bidirectional"))
      (node (ref "J3") (pin "P$2") (pinfunction "EE3_P$2") (pintype "bidirectional"))
    )
    (net (code "106") (name "Net-(J2-EE4)") (class "Default")
      (node (ref "J2") (pin "P$26") (pinfunction "EE4_P$26") (pintype "bidirectional"))
      (node (ref "J3") (pin "P$3") (pinfunction "EE4_P$3") (pintype "bidirectional"))
    )
    (net (code "107") (name "unconnected-(IC3-Y7-Pad7)") (class "Default")
      (node (ref "IC3") (pin "7") (pinfunction "Y7_7") (pintype "bidirectional"))
    )
    (net (code "108") (name "unconnected-(IC4-Y7-Pad7)") (class "Default")
      (node (ref "IC4") (pin "7") (pinfunction "Y7_7") (pintype "bidirectional"))
    )
    (net (code "109") (name "unconnected-(IC5-Y7-Pad7)") (class "Default")
      (node (ref "IC5") (pin "7") (pinfunction "Y7_7") (pintype "bidirectional"))
    )
    (net (code "110") (name "unconnected-(IC6-Y7-Pad7)") (class "Default")
      (node (ref "IC6") (pin "7") (pinfunction "Y7_7") (pintype "bidirectional"))
    )
    (net (code "111") (name "unconnected-(IC7-I8-Pad8)") (class "Default")
      (node (ref "IC7") (pin "8") (pinfunction "I8_8") (pintype "bidirectional"))
    )
    (net (code "112") (name "unconnected-(IC7-O8-Pad11)") (class "Default")
      (node (ref "IC7") (pin "11") (pinfunction "O8_11") (pintype "bidirectional"))
    )
    (net (code "113") (name "unconnected-(IC8-COM-Pad9)") (class "Default")
      (node (ref "IC8") (pin "9") (pinfunction "COM_9") (pintype "bidirectional"))
    )
    (net (code "114") (name "unconnected-(IC9-I8-Pad8)") (class "Default")
      (node (ref "IC9") (pin "8") (pinfunction "I8_8") (pintype "bidirectional"))
    )
    (net (code "115") (name "unconnected-(IC9-O8-Pad11)") (class "Default")
      (node (ref "IC9") (pin "11") (pinfunction "O8_11") (pintype "bidirectional"))
    )
    (net (code "116") (name "unconnected-(IC10-COM-Pad9)") (class "Default")
      (node (ref "IC10") (pin "9") (pinfunction "COM_9") (pintype "bidirectional"))
    )
    (net (code "117") (name "unconnected-(IC11-Y7-Pad7)") (class "Default")
      (node (ref "IC11") (pin "7") (pinfunction "Y7_7") (pintype "bidirectional"))
    )
    (net (code "118") (name "unconnected-(IC12-Y7-Pad7)") (class "Default")
      (node (ref "IC12") (pin "7") (pinfunction "Y7_7") (pintype "bidirectional"))
    )
    (net (code "119") (name "unconnected-(IC13-Y3-Pad12)") (class "Default")
      (node (ref "IC13") (pin "12") (pinfunction "Y3_12") (pintype "bidirectional"))
    )
    (net (code "120") (name "unconnected-(IC13-Y4-Pad11)") (class "Default")
      (node (ref "IC13") (pin "11") (pinfunction "Y4_11") (pintype "bidirectional"))
    )
    (net (code "121") (name "unconnected-(IC14-I8-Pad8)") (class "Default")
      (node (ref "IC14") (pin "8") (pinfunction "I8_8") (pintype "bidirectional"))
    )
    (net (code "122") (name "unconnected-(IC14-O8-Pad11)") (class "Default")
      (node (ref "IC14") (pin "11") (pinfunction "O8_11") (pintype "bidirectional"))
    )
    (net (code "123") (name "unconnected-(IC15-COM-Pad9)") (class "Default")
      (node (ref "IC15") (pin "9") (pinfunction "COM_9") (pintype "bidirectional"))
    )
    (net (code "124") (name "unconnected-(IC16-I4-Pad4)") (class "Default")
      (node (ref "IC16") (pin "4") (pinfunction "I4_4") (pintype "bidirectional"))
    )
    (net (code "125") (name "unconnected-(IC16-I5-Pad5)") (class "Default")
      (node (ref "IC16") (pin "5") (pinfunction "I5_5") (pintype "bidirectional"))
    )
    (net (code "126") (name "unconnected-(IC16-I6-Pad6)") (class "Default")
      (node (ref "IC16") (pin "6") (pinfunction "I6_6") (pintype "bidirectional"))
    )
    (net (code "127") (name "unconnected-(IC16-I7-Pad7)") (class "Default")
      (node (ref "IC16") (pin "7") (pinfunction "I7_7") (pintype "bidirectional"))
    )
    (net (code "128") (name "unconnected-(IC16-I8-Pad8)") (class "Default")
      (node (ref "IC16") (pin "8") (pinfunction "I8_8") (pintype "bidirectional"))
    )
    (net (code "129") (name "unconnected-(IC16-O4-Pad15)") (class "Default")
      (node (ref "IC16") (pin "15") (pinfunction "O4_15") (pintype "bidirectional"))
    )
    (net (code "130") (name "unconnected-(IC16-O5-Pad14)") (class "Default")
      (node (ref "IC16") (pin "14") (pinfunction "O5_14") (pintype "bidirectional"))
    )
    (net (code "131") (name "unconnected-(IC16-O6-Pad13)") (class "Default")
      (node (ref "IC16") (pin "13") (pinfunction "O6_13") (pintype "bidirectional"))
    )
    (net (code "132") (name "unconnected-(IC16-O7-Pad12)") (class "Default")
      (node (ref "IC16") (pin "12") (pinfunction "O7_12") (pintype "bidirectional"))
    )
    (net (code "133") (name "unconnected-(IC16-O8-Pad11)") (class "Default")
      (node (ref "IC16") (pin "11") (pinfunction "O8_11") (pintype "bidirectional"))
    )
    (net (code "134") (name "unconnected-(IC17-COM-Pad9)") (class "Default")
      (node (ref "IC17") (pin "9") (pinfunction "COM_9") (pintype "bidirectional"))
    )
    (net (code "135") (name "unconnected-(IC17-I4-Pad4)") (class "Default")
      (node (ref "IC17") (pin "4") (pinfunction "I4_4") (pintype "bidirectional"))
    )
    (net (code "136") (name "unconnected-(IC17-I5-Pad5)") (class "Default")
      (node (ref "IC17") (pin "5") (pinfunction "I5_5") (pintype "bidirectional"))
    )
    (net (code "137") (name "unconnected-(IC17-I6-Pad6)") (class "Default")
      (node (ref "IC17") (pin "6") (pinfunction "I6_6") (pintype "bidirectional"))
    )
    (net (code "138") (name "unconnected-(IC17-I7-Pad7)") (class "Default")
      (node (ref "IC17") (pin "7") (pinfunction "I7_7") (pintype "bidirectional"))
    )
    (net (code "139") (name "unconnected-(IC17-O4-Pad13)") (class "Default")
      (node (ref "IC17") (pin "13") (pinfunction "O4_13") (pintype "bidirectional"))
    )
    (net (code "140") (name "unconnected-(IC17-O5-Pad12)") (class "Default")
      (node (ref "IC17") (pin "12") (pinfunction "O5_12") (pintype "bidirectional"))
    )
    (net (code "141") (name "unconnected-(IC17-O6-Pad11)") (class "Default")
      (node (ref "IC17") (pin "11") (pinfunction "O6_11") (pintype "bidirectional"))
    )
    (net (code "142") (name "unconnected-(IC17-O7-Pad10)") (class "Default")
      (node (ref "IC17") (pin "10") (pinfunction "O7_10") (pintype "bidirectional"))
    )
    (net (code "143") (name "unconnected-(IC18-Y0-Pad15)") (class "Default")
      (node (ref "IC18") (pin "15") (pinfunction "Y0_15") (pintype "bidirectional"))
    )
    (net (code "144") (name "unconnected-(J1-NC1-PadP$8)") (class "Default")
      (node (ref "J1") (pin "P$8") (pinfunction "NC1_P$8") (pintype "bidirectional"))
    )
    (net (code "145") (name "unconnected-(J1-NC2-PadP$28)") (class "Default")
      (node (ref "J1") (pin "P$28") (pinfunction "NC2_P$28") (pintype "bidirectional"))
    )
  )
)
